# Circuitry.net
KiCad netlist of a schematic drawn in Altium Designer
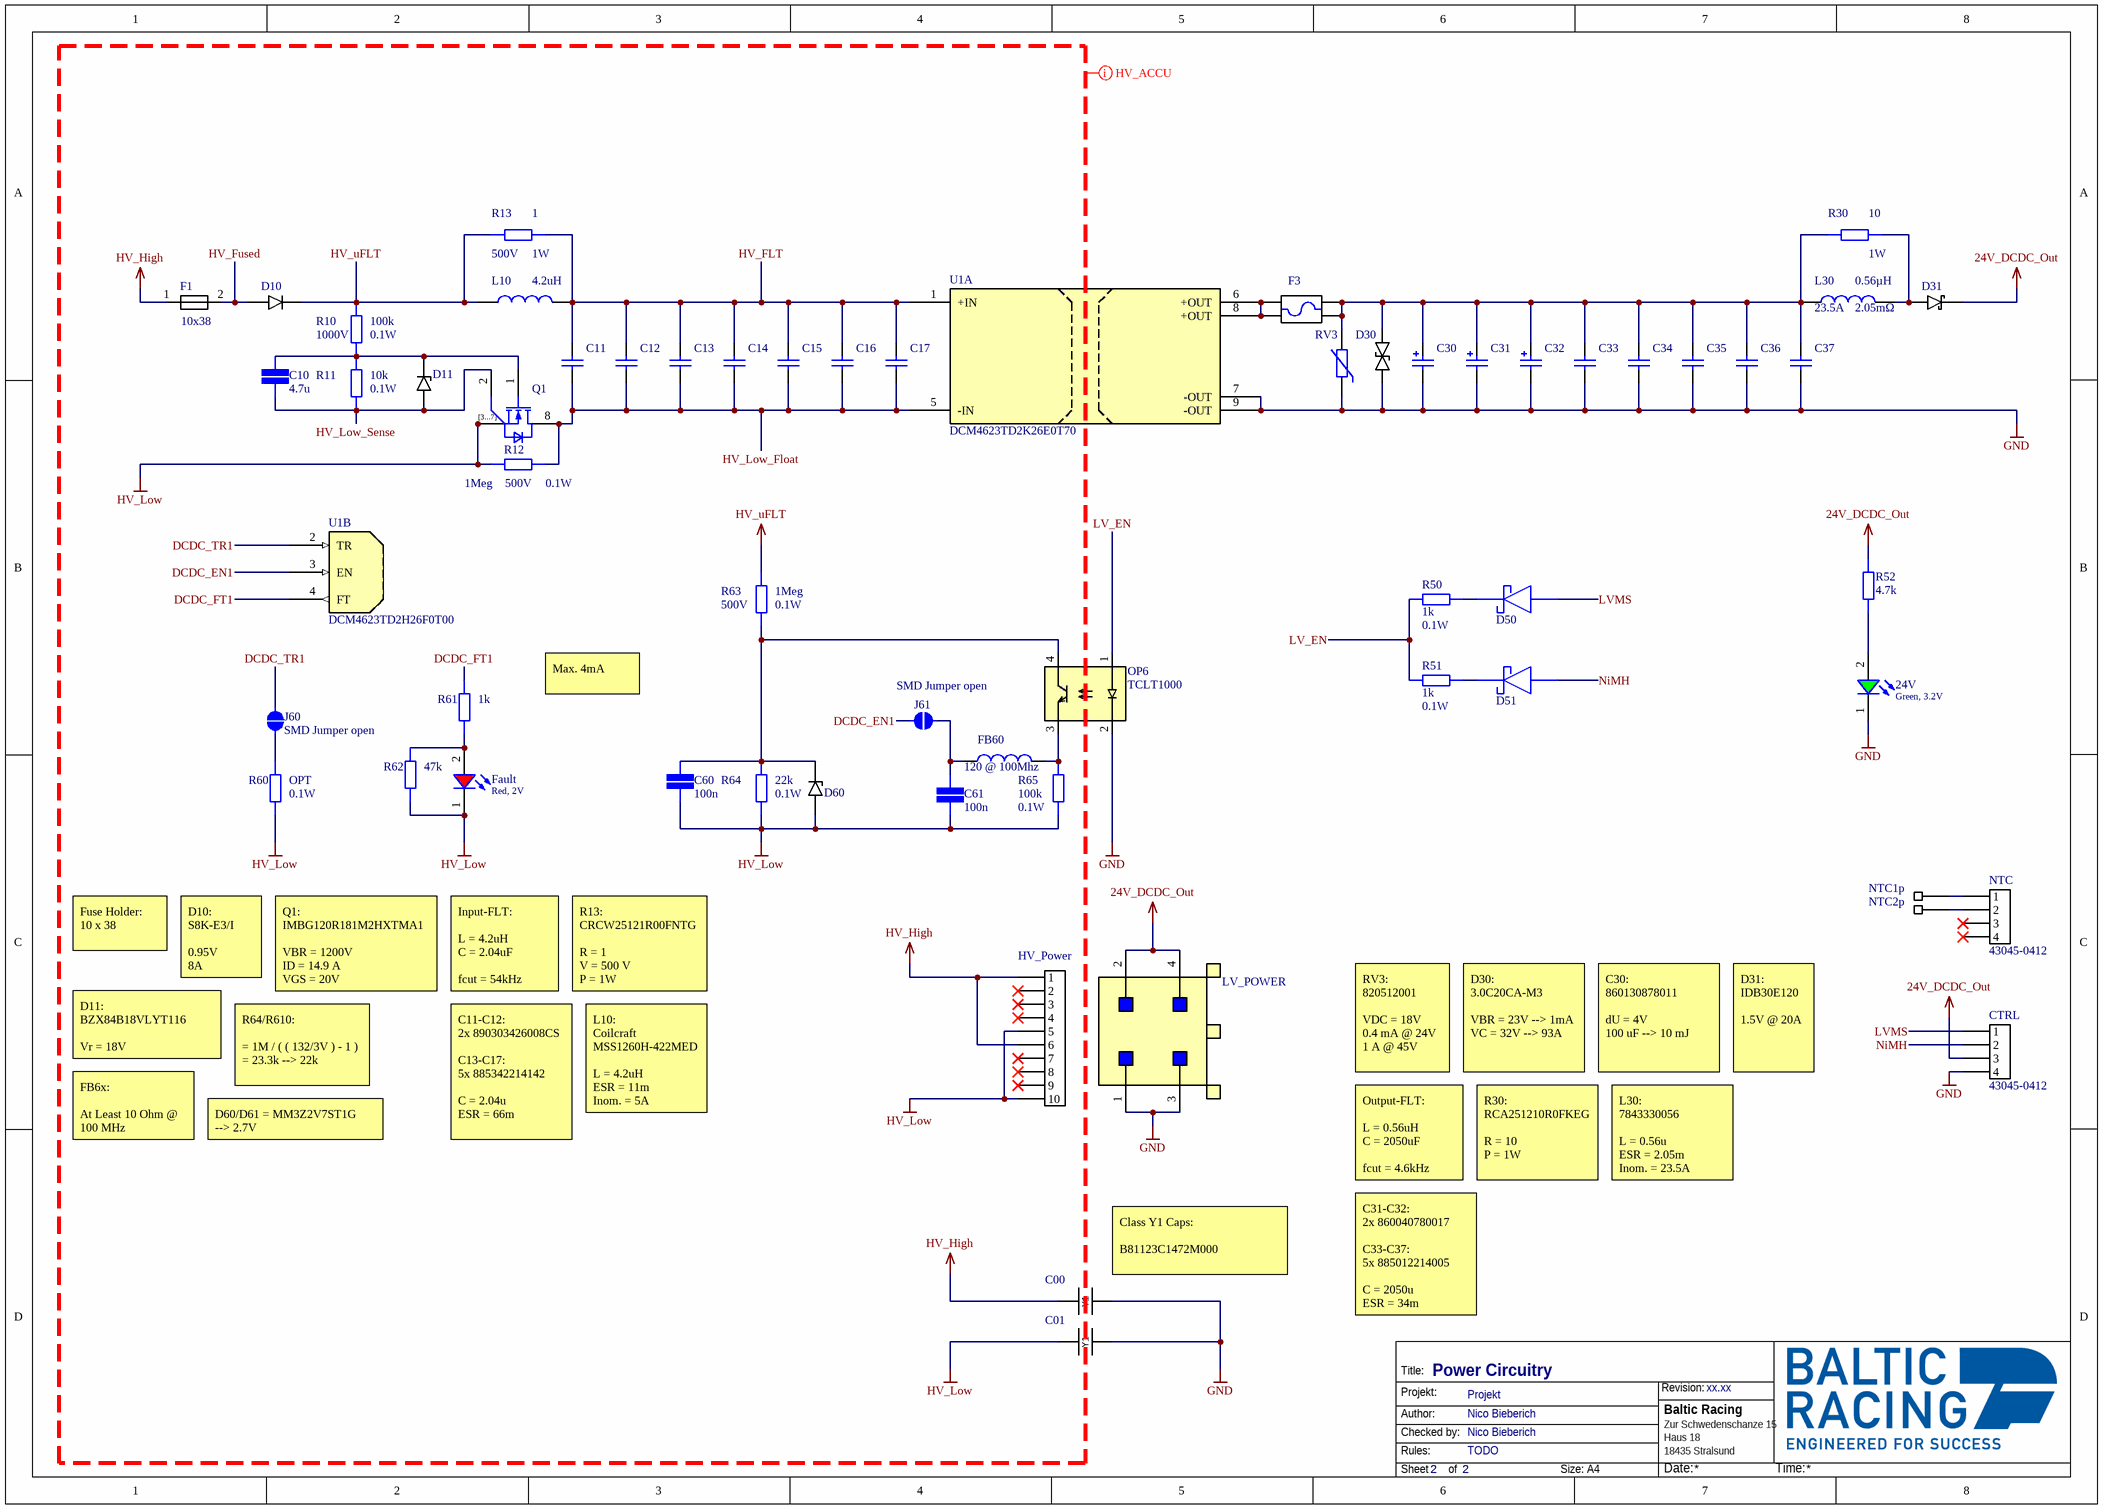
[diagram p0: Circuitry.SchDoc]

(export (version "E")
  (design (tool "Eeschema 10.0.6"))
  (components
    (comp (ref "24V")
      (value "Green, 3.2V")
      (footprint "WL-SMCW_0603_H=0.7mm")
      (description "WL-SMCW SMT Mono-color Chip LED Waterclear, size 0603, Green, 3.2V, 140deg")
      (fields (field (name "PART NUMBER") "150060GS75000") (field (name "PUBLISHER") "Wurth Elektronik"))
      (libsource (lib "Altium_WL-SMCW (rev20a)") (part "150060GS75000"))
    )
    (comp (ref "C00")
      (value "B81123C1472M000")
      (footprint "B81123C1472M000")
      (description "EPCOS/TDK B81123C1472M000\r\nClass Y1 Capacitor")
      (libsource (lib "libNico") (part "B81123C1472M000"))
    )
    (comp (ref "C01")
      (value "B81123C1472M000")
      (footprint "B81123C1472M000")
      (description "EPCOS/TDK B81123C1472M000\r\nClass Y1 Capacitor")
      (libsource (lib "libNico") (part "B81123C1472M000"))
    )
    (comp (ref "C10")
      (value "4.7u")
      (footprint "CAP 1206/3216")
      (description "Capacitor with multiple Footprints")
      (fields (field (name "VOLTAGE") "32V") (field (name "Comment") "SMD Capacitor"))
      (libsource (lib "Standardbauteile") (part "SMD Capacitor"))
    )
    (comp (ref "C11")
      (value "630V DC, 0.47 uF")
      (footprint "WCAP-FTBE_26x9x18")
      (description "WCAP-FTBE Film Capacitors, 26x9x18mm, 630V DC, 0.47 uF")
      (fields (field (name "PART NUMBER") "890303426008CS") (field (name "PUBLISHER") "Wurth Elektronik"))
      (libsource (lib "ALTIUM-WCAP-FTBE-rev17a") (part "890303426008CS"))
    )
    (comp (ref "C12")
      (value "630V DC, 0.47 uF")
      (footprint "WCAP-FTBE_26x9x18")
      (description "WCAP-FTBE Film Capacitors, 26x9x18mm, 630V DC, 0.47 uF")
      (fields (field (name "PART NUMBER") "890303426008CS") (field (name "PUBLISHER") "Wurth Elektronik"))
      (libsource (lib "ALTIUM-WCAP-FTBE-rev17a") (part "890303426008CS"))
    )
    (comp (ref "C13")
      (value "220nF")
      (footprint "WCAP-CSMH_2220_L5.7W5H2")
      (fields
        (field (name "MANUFACTURER PART NUMBER") "885342214142")
        (field (name "MANUFACTURER") "Wurth Elektronik")
      )
      (libsource (lib "Altium_WCAP-CSMH (rev22d)") (part "885342214142"))
    )
    (comp (ref "C14")
      (value "220nF")
      (footprint "WCAP-CSMH_2220_L5.7W5H2")
      (fields
        (field (name "MANUFACTURER PART NUMBER") "885342214142")
        (field (name "MANUFACTURER") "Wurth Elektronik")
      )
      (libsource (lib "Altium_WCAP-CSMH (rev22d)") (part "885342214142"))
    )
    (comp (ref "C15")
      (value "220nF")
      (footprint "WCAP-CSMH_2220_L5.7W5H2")
      (fields
        (field (name "MANUFACTURER PART NUMBER") "885342214142")
        (field (name "MANUFACTURER") "Wurth Elektronik")
      )
      (libsource (lib "Altium_WCAP-CSMH (rev22d)") (part "885342214142"))
    )
    (comp (ref "C16")
      (value "220nF")
      (footprint "WCAP-CSMH_2220_L5.7W5H2")
      (fields
        (field (name "MANUFACTURER PART NUMBER") "885342214142")
        (field (name "MANUFACTURER") "Wurth Elektronik")
      )
      (libsource (lib "Altium_WCAP-CSMH (rev22d)") (part "885342214142"))
    )
    (comp (ref "C17")
      (value "220nF")
      (footprint "WCAP-CSMH_2220_L5.7W5H2")
      (fields
        (field (name "MANUFACTURER PART NUMBER") "885342214142")
        (field (name "MANUFACTURER") "Wurth Elektronik")
      )
      (libsource (lib "Altium_WCAP-CSMH (rev22d)") (part "885342214142"))
    )
    (comp (ref "C30")
      (value "100uF, 100V")
      (footprint "WCAP-ATET_13x25")
      (description "WCAP-ATET THT Aluminum Electrolytic Capacitors, D13mm x L25mm, 100uF, +/-20%, 100VDC")
      (fields (field (name "PART NUMBER") "860130878011") (field (name "PUBLISHER") "Wurth Elektronik"))
      (libsource (lib "Altium_WCAP-ATET (rev19a)") (part "860130878011"))
    )
    (comp (ref "C31")
      (value "1000uF, 63V")
      (footprint "WCAP-ATUL_16x35.5")
      (description "WCAP-ATUL THT Aluminum Electrolytic Capacitors, D16mm x L35.5mm, 1000uF, +/-20%, 63VDC")
      (fields (field (name "PART NUMBER") "860040780017") (field (name "PUBLISHER") "Wurth Elektronik"))
      (libsource (lib "Altium_WCAP-ATUL_rev19a") (part "860040780017"))
    )
    (comp (ref "C32")
      (value "1000uF, 63V")
      (footprint "WCAP-ATUL_16x35.5")
      (description "WCAP-ATUL THT Aluminum Electrolytic Capacitors, D16mm x L35.5mm, 1000uF, +/-20%, 63VDC")
      (fields (field (name "PART NUMBER") "860040780017") (field (name "PUBLISHER") "Wurth Elektronik"))
      (libsource (lib "Altium_WCAP-ATUL_rev19a") (part "860040780017"))
    )
    (comp (ref "C33")
      (value "10uF")
      (footprint "WCAP-CSGP_2220_L5.7W5H2.8")
      (description "WCAP-CSGP Multilayer Ceramic Chip Capacitor, General Purpose, size 2220, X7R Class II, 10uF, 50VDC")
      (fields
        (field (name "MANUFACTURER PART NUMBER") "885012214005")
        (field (name "MANUFACTURER") "Wurth Elektronik")
      )
      (libsource (lib "Altium_WCAP-CSGP (rev24b)") (part "885012214005"))
    )
    (comp (ref "C34")
      (value "10uF")
      (footprint "WCAP-CSGP_2220_L5.7W5H2.8")
      (description "WCAP-CSGP Multilayer Ceramic Chip Capacitor, General Purpose, size 2220, X7R Class II, 10uF, 50VDC")
      (fields
        (field (name "MANUFACTURER PART NUMBER") "885012214005")
        (field (name "MANUFACTURER") "Wurth Elektronik")
      )
      (libsource (lib "Altium_WCAP-CSGP (rev24b)") (part "885012214005"))
    )
    (comp (ref "C35")
      (value "10uF")
      (footprint "WCAP-CSGP_2220_L5.7W5H2.8")
      (description "WCAP-CSGP Multilayer Ceramic Chip Capacitor, General Purpose, size 2220, X7R Class II, 10uF, 50VDC")
      (fields
        (field (name "MANUFACTURER PART NUMBER") "885012214005")
        (field (name "MANUFACTURER") "Wurth Elektronik")
      )
      (libsource (lib "Altium_WCAP-CSGP (rev24b)") (part "885012214005"))
    )
    (comp (ref "C36")
      (value "10uF")
      (footprint "WCAP-CSGP_2220_L5.7W5H2.8")
      (description "WCAP-CSGP Multilayer Ceramic Chip Capacitor, General Purpose, size 2220, X7R Class II, 10uF, 50VDC")
      (fields
        (field (name "MANUFACTURER PART NUMBER") "885012214005")
        (field (name "MANUFACTURER") "Wurth Elektronik")
      )
      (libsource (lib "Altium_WCAP-CSGP (rev24b)") (part "885012214005"))
    )
    (comp (ref "C37")
      (value "10uF")
      (footprint "WCAP-CSGP_2220_L5.7W5H2.8")
      (description "WCAP-CSGP Multilayer Ceramic Chip Capacitor, General Purpose, size 2220, X7R Class II, 10uF, 50VDC")
      (fields
        (field (name "MANUFACTURER PART NUMBER") "885012214005")
        (field (name "MANUFACTURER") "Wurth Elektronik")
      )
      (libsource (lib "Altium_WCAP-CSGP (rev24b)") (part "885012214005"))
    )
    (comp (ref "C60")
      (value "100n")
      (footprint "CAP 0603/1608")
      (description "Capacitor with multiple Footprints")
      (fields (field (name "Comment") "SMD Capacitor"))
      (libsource (lib "Standardbauteile") (part "SMD Capacitor"))
    )
    (comp (ref "C61")
      (value "100n")
      (footprint "CAP 0603/1608")
      (description "Capacitor with multiple Footprints")
      (fields (field (name "Comment") "SMD Capacitor"))
      (libsource (lib "Standardbauteile") (part "SMD Capacitor"))
    )
    (comp (ref "CTRL")
      (value "43045-0412")
      (footprint "43045-0412")
      (libsource (lib "molex_43045") (part "43045-0412"))
    )
    (comp (ref "D10")
      (value "S8K-E3/I")
      (footprint "S8K-E3/I")
      (description "Vishay S8K-E3/I\r\nDiode, 950mV, 8A, 800V")
      (libsource (lib "libNico") (part "S8K-E3/I"))
    )
    (comp (ref "D11")
      (value "BZX84B18VLYT116")
      (footprint "SOT-23-3")
      (description "ROHM BZX84B18VLYT116\r\nZ-Diode, 18V")
      (libsource (lib "libNico") (part "BZX84B18VLYT116"))
    )
    (comp (ref "D30")
      (value "3.0C20CA-M3")
      (footprint "3.0C20CA-M3")
      (description "Vishay 3.0C20CA-M3\r\nBidirect. TVS, 20V, 3kW")
      (libsource (lib "libNico") (part "3.0C20CA-M3"))
    )
    (comp (ref "D31")
      (value "IDB30E120")
      (footprint "Infineon IDB30E120")
      (description "Infineon IDB30E120\r\n1200V, 30A @ 1.7V")
      (libsource (lib "libNico") (part "IDB30E120"))
    )
    (comp (ref "D50")
      (value "CUS521,H3F")
      (footprint "SOD-323-2")
      (description "Toshiba CUS521,H3F\r\nShottky-Diode\r\nForward: 390mV, Reverse: 30V")
      (libsource (lib "libNico") (part "CUS521,H3F"))
    )
    (comp (ref "D51")
      (value "CUS521,H3F")
      (footprint "SOD-323-2")
      (description "Toshiba CUS521,H3F\r\nShottky-Diode\r\nForward: 390mV, Reverse: 30V")
      (libsource (lib "libNico") (part "CUS521,H3F"))
    )
    (comp (ref "D60")
      (value "MM3Z2V7ST1G")
      (footprint "SOD-323-2")
      (description "onsemi MM3Z2V7ST1G\r\nZ-Diode, 2,7V")
      (libsource (lib "libNico") (part "MM3Z2V7ST1G"))
    )
    (comp (ref "F1")
      (value "Fuse 10x38")
      (footprint "Fuse Holder 10x38")
      (fields (field (name "FORMAT") "10x38"))
      (libsource (lib "libNico") (part "Fuse 10x38"))
    )
    (comp (ref "F3")
      (value "Keystone 3557-2")
      (footprint "Keystone 3557-2")
      (description "Keystone 3557-2\r\nFuse Holder")
      (libsource (lib "libNico") (part "Keystone 3557-2"))
    )
    (comp (ref "Fault")
      (value "Red, 2V")
      (footprint "WL-SMCW_0603_H=0.7mm")
      (description "WL-SMCW SMT Mono-color Chip LED Waterclear, size 0603, Red, 2V, 140deg")
      (fields (field (name "PART NUMBER") "150060RS75000") (field (name "PUBLISHER") "Wurth Elektronik"))
      (libsource (lib "Altium_WL-SMCW (rev20a)") (part "150060RS75000"))
    )
    (comp (ref "FB60")
      (value "120 @ 100Mhz")
      (footprint "WE-CBA_0603_L1.6W0.8H0.8_HF/HS/WB")
      (description "WE-CBA SMT EMI Suppression Ferrite Bead, size 0603, 120Ohm, 0.5A")
      (fields
        (field (name "MANUFACTURER PART NUMBER") "782631131")
        (field (name "MANUFACTURER") "Wurth Elektronik")
      )
      (libsource (lib "Altium_WE-CBA (rev22d)") (part "782631131"))
    )
    (comp (ref "HV_Power")
      (value "43045-1012")
      (footprint "43045-1012")
      (libsource (lib "molex_43045") (part "43045-1012"))
    )
    (comp (ref "J60")
      (value "SMD Jumper open")
      (footprint "SMD-JUMPER-OPEN")
      (libsource (lib "Standardbauteile") (part "SMD Jumper open"))
    )
    (comp (ref "J61")
      (value "SMD Jumper open")
      (footprint "SMD-JUMPER-OPEN")
      (libsource (lib "Standardbauteile") (part "SMD Jumper open"))
    )
    (comp (ref "L10")
      (value "4.2uH")
      (footprint "Coilcraft MSS1260H-422MED")
      (description "Coilcraft MSS1260H-422MED\r\nShielded Inductor, 4.2uH, 11mOhm, 5A")
      (fields (field (name "Comment") "MSS1260H-422MED"))
      (libsource (lib "libNico") (part "MSS1260H-422MED"))
    )
    (comp (ref "L30")
      (value "0.56µH, 23.5A")
      (footprint "WE-CHSA_1011")
      (description "WE-CHSA SMT High Current Inductor, size 1011, 0.56µH, 23.5A, 2.05mΩ")
      (fields
        (field (name "MANUFACTURER PART NUMBER") "7843330056")
        (field (name "MANUFACTURER") "Wurth Elektronik")
        (field (name "DC RESISTANCE MAX") "2.05mΩ")
        (field (name "INDUCTANCE") "0.56µH")
        (field (name "RATED CURRENT") "23.5A")
      )
      (libsource (lib "Altium_WE-CHSA (rev22d)") (part "7843330056"))
    )
    (comp (ref "LV_POWER")
      (value "LV_POWER")
      (footprint "1720650004")
      (libsource (lib "libNico") (part "1720650004"))
    )
    (comp (ref "NTC")
      (value "43045-0412")
      (footprint "43045-0412")
      (libsource (lib "molex_43045") (part "43045-0412"))
    )
    (comp (ref "NTC1p")
      (value "Pad")
      (footprint "Generic_Pad_1.5x1.5")
      (description "Pad 1.5mm x 1.5mm")
      (libsource (lib "libNico") (part "Generic_Pad_1.5x1.5"))
    )
    (comp (ref "NTC2p")
      (value "Pad")
      (footprint "Generic_Pad_1.5x1.5")
      (description "Pad 1.5mm x 1.5mm")
      (libsource (lib "libNico") (part "Generic_Pad_1.5x1.5"))
    )
    (comp (ref "OP6")
      (value "TCLT1000")
      (footprint "SOP-4L")
      (description "Opto-Isolator\r\nVishay TLCT100 series\r\n600V, 5mA, V_ISO= 5 kV (RMS)")
      (libsource (lib "libNico") (part "TCLT1000"))
    )
    (comp (ref "Q1")
      (value "IMBG120R181M2H")
      (footprint "TO127P1500X470-8N-2-V1")
      (description "Infineon IMBG120R181M2HXTMA1\r\nCoolSiC, 1200V, 15A, 181.4mOhm")
      (libsource (lib "libNico") (part "IMBG120R181M2H"))
    )
    (comp (ref "R10")
      (value "100k")
      (footprint "STACKPOLE CSR1206")
      (description "Resistor with multiple footprints")
      (fields
        (field (name "VOLTAGE") "1000V")
        (field (name "POWER") "0.1W")
        (field (name "Comment") "SMD Resistor")
      )
      (libsource (lib "Standardbauteile") (part "SMD Resistor"))
    )
    (comp (ref "R11")
      (value "10k")
      (footprint "STACKPOLE CSR1206")
      (description "Resistor with multiple footprints")
      (fields
        (field (name "VOLTAGE") "1000V")
        (field (name "POWER") "0.1W")
        (field (name "Comment") "SMD Resistor")
      )
      (libsource (lib "Standardbauteile") (part "SMD Resistor"))
    )
    (comp (ref "R12")
      (value "1Meg")
      (footprint "STACKPOLE CSRN2512")
      (description "Resistor with multiple footprints")
      (fields
        (field (name "VOLTAGE") "500V")
        (field (name "POWER") "0.1W")
        (field (name "Comment") "SMD Resistor")
      )
      (libsource (lib "Standardbauteile") (part "SMD Resistor"))
    )
    (comp (ref "R13")
      (value "1")
      (footprint "STACKPOLE CSRN2512")
      (description "Resistor with multiple footprints")
      (fields
        (field (name "VOLTAGE") "500V")
        (field (name "POWER") "1W")
        (field (name "Comment") "SMD Resistor")
      )
      (libsource (lib "Standardbauteile") (part "SMD Resistor"))
    )
    (comp (ref "R30")
      (value "10")
      (footprint "STACKPOLE CSRN2512")
      (description "Resistor with multiple footprints")
      (fields (field (name "POWER") "1W") (field (name "Comment") "SMD Resistor"))
      (libsource (lib "Standardbauteile") (part "SMD Resistor"))
    )
    (comp (ref "R50")
      (value "1k")
      (footprint "STACKPOLE CSR0603")
      (description "Resistor with multiple footprints")
      (fields (field (name "POWER") "0.1W") (field (name "Comment") "SMD Resistor"))
      (libsource (lib "Standardbauteile") (part "SMD Resistor"))
    )
    (comp (ref "R51")
      (value "1k")
      (footprint "STACKPOLE CSR0603")
      (description "Resistor with multiple footprints")
      (fields (field (name "POWER") "0.1W") (field (name "Comment") "SMD Resistor"))
      (libsource (lib "Standardbauteile") (part "SMD Resistor"))
    )
    (comp (ref "R52")
      (value "4.7k")
      (footprint "STACKPOLE CSR0603")
      (description "Resistor with multiple footprints")
      (fields (field (name "POWER") "0.1 W") (field (name "Comment") "SMD Resistor"))
      (libsource (lib "Standardbauteile") (part "SMD Resistor"))
    )
    (comp (ref "R60")
      (value "OPT")
      (footprint "STACKPOLE CSR0603")
      (description "Resistor with multiple footprints")
      (fields (field (name "POWER") "0.1W") (field (name "Comment") "SMD Resistor"))
      (libsource (lib "Standardbauteile") (part "SMD Resistor"))
    )
    (comp (ref "R61")
      (value "1k")
      (footprint "STACKPOLE CSR0603")
      (description "Resistor with multiple footprints")
      (fields (field (name "POWER") "0.1W") (field (name "Comment") "SMD Resistor"))
      (libsource (lib "Standardbauteile") (part "SMD Resistor"))
    )
    (comp (ref "R62")
      (value "47k")
      (footprint "STACKPOLE CSR0603")
      (description "Resistor with multiple footprints")
      (fields (field (name "POWER") "0.1W") (field (name "Comment") "SMD Resistor"))
      (libsource (lib "Standardbauteile") (part "SMD Resistor"))
    )
    (comp (ref "R63")
      (value "1Meg")
      (footprint "STACKPOLE CSRN2512")
      (description "Resistor with multiple footprints")
      (fields
        (field (name "VOLTAGE") "500V")
        (field (name "POWER") "0.1W")
        (field (name "Comment") "SMD Resistor")
      )
      (libsource (lib "Standardbauteile") (part "SMD Resistor"))
    )
    (comp (ref "R64")
      (value "22k")
      (footprint "STACKPOLE CSR0603")
      (description "Resistor with multiple footprints")
      (fields (field (name "POWER") "0.1W") (field (name "Comment") "SMD Resistor"))
      (libsource (lib "Standardbauteile") (part "SMD Resistor"))
    )
    (comp (ref "R65")
      (value "100k")
      (footprint "STACKPOLE CSR0603")
      (description "Resistor with multiple footprints")
      (fields (field (name "POWER") "0.1W") (field (name "Comment") "SMD Resistor"))
      (libsource (lib "Standardbauteile") (part "SMD Resistor"))
    )
    (comp (ref "RV3")
      (value "20VAC, 26VDC")
      (footprint "D12.5W5.1H15.5P0.8")
      (description "WE-VD Disk Varistor, THT, 20VAC, 26VDC, 4250pF")
      (fields
        (field (name "MANUFACTURER PART NUMBER") "820512001")
        (field (name "MANUFACTURER") "Wurth Elektronik")
      )
      (libsource (lib "Altium_WE-VD (rev23a)") (part "820512001"))
    )
    (comp (ref "U1")
      (value "DCM4623")
      (footprint "DCM4623")
      (description "VICOR DCM® DC-DC Converter Module")
      (fields (field (name "MODEL") "DCM4623TD2K26E0T70"))
      (libsource (lib "libNico") (part "DCM4623"))
    )
  )
  (nets
    (net (code "1") (name "/DCDC_EN1") (class "Default")
      (node (ref "J61") (pin "2") (pinfunction "2_2") (pintype "passive"))
      (node (ref "U1") (pin "3") (pinfunction "EN_3") (pintype "input"))
    )
    (net (code "2") (name "/DCDC_FT1") (class "Default")
      (node (ref "R61") (pin "2") (pinfunction "2_2") (pintype "passive"))
      (node (ref "U1") (pin "4") (pinfunction "FT_4") (pintype "output"))
    )
    (net (code "3") (name "/DCDC_TR1") (class "Default")
      (node (ref "J60") (pin "2") (pinfunction "2_2") (pintype "passive"))
      (node (ref "U1") (pin "2") (pinfunction "TR_2") (pintype "input"))
    )
    (net (code "4") (name "/HV_FLT") (class "Default")
      (node (ref "C11") (pin "2") (pinfunction "2_2") (pintype "passive"))
      (node (ref "C12") (pin "2") (pinfunction "2_2") (pintype "passive"))
      (node (ref "C13") (pin "2") (pinfunction "2_2") (pintype "passive"))
      (node (ref "C14") (pin "2") (pinfunction "2_2") (pintype "passive"))
      (node (ref "C15") (pin "2") (pinfunction "2_2") (pintype "passive"))
      (node (ref "C16") (pin "2") (pinfunction "2_2") (pintype "passive"))
      (node (ref "C17") (pin "2") (pinfunction "2_2") (pintype "passive"))
      (node (ref "L10") (pin "2") (pinfunction "2_2") (pintype "passive"))
      (node (ref "R13") (pin "1") (pinfunction "1_1") (pintype "passive"))
      (node (ref "U1") (pin "1") (pinfunction "+IN_1") (pintype "power_in"))
    )
    (net (code "5") (name "/HV_Fused") (class "Default")
      (node (ref "D10") (pin "2") (pinfunction "A_2") (pintype "passive"))
      (node (ref "F1") (pin "2") (pinfunction "2_2") (pintype "passive"))
    )
    (net (code "6") (name "/HV_Low_Float") (class "Default")
      (node (ref "C11") (pin "1") (pinfunction "1_1") (pintype "passive"))
      (node (ref "C12") (pin "1") (pinfunction "1_1") (pintype "passive"))
      (node (ref "C13") (pin "1") (pinfunction "1_1") (pintype "passive"))
      (node (ref "C14") (pin "1") (pinfunction "1_1") (pintype "passive"))
      (node (ref "C15") (pin "1") (pinfunction "1_1") (pintype "passive"))
      (node (ref "C16") (pin "1") (pinfunction "1_1") (pintype "passive"))
      (node (ref "C17") (pin "1") (pinfunction "1_1") (pintype "passive"))
      (node (ref "Q1") (pin "8") (pinfunction "DRAIN_8") (pintype "passive"))
      (node (ref "R12") (pin "1") (pinfunction "1_1") (pintype "passive"))
      (node (ref "U1") (pin "5") (pinfunction "-IN_5") (pintype "passive"))
    )
    (net (code "7") (name "/HV_Low_Sense") (class "Default")
      (node (ref "C10") (pin "1") (pinfunction "1_1") (pintype "passive"))
      (node (ref "D11") (pin "1") (pinfunction "A_1") (pintype "passive"))
      (node (ref "Q1") (pin "2") (pinfunction "SENSE_2") (pintype "passive"))
      (node (ref "R11") (pin "1") (pinfunction "1_1") (pintype "passive"))
    )
    (net (code "8") (name "/LVMS") (class "Default")
      (node (ref "CTRL") (pin "1") (pinfunction "1_1") (pintype "passive"))
      (node (ref "D50") (pin "2A") (pinfunction "A_2A") (pintype "passive"))
    )
    (net (code "9") (name "/LV_EN") (class "Default")
      (node (ref "OP6") (pin "1") (pinfunction "DA_1") (pintype "passive"))
      (node (ref "R50") (pin "2") (pinfunction "2_2") (pintype "passive"))
      (node (ref "R51") (pin "2") (pinfunction "2_2") (pintype "passive"))
    )
    (net (code "10") (name "/NiMH") (class "Default")
      (node (ref "CTRL") (pin "2") (pinfunction "2_2") (pintype "passive"))
      (node (ref "D51") (pin "2A") (pinfunction "A_2A") (pintype "passive"))
    )
    (net (code "11") (name "24V_DCDC_Out") (class "Default")
      (node (ref "CTRL") (pin "3") (pinfunction "3_3") (pintype "passive"))
      (node (ref "D31") (pin "2") (pinfunction "C_2") (pintype "passive"))
      (node (ref "LV_POWER") (pin "2") (pinfunction "2_2") (pintype "passive"))
      (node (ref "LV_POWER") (pin "4") (pinfunction "4_4") (pintype "passive"))
      (node (ref "R52") (pin "2") (pinfunction "2_2") (pintype "passive"))
    )
    (net (code "12") (name "GND") (class "Default")
      (node (ref "24V") (pin "1") (pinfunction "K_1") (pintype "passive"))
      (node (ref "C00") (pin "2") (pinfunction "2_2") (pintype "passive"))
      (node (ref "C01") (pin "2") (pinfunction "2_2") (pintype "passive"))
      (node (ref "C30") (pin "1") (pinfunction "N_1") (pintype "passive"))
      (node (ref "C31") (pin "1") (pinfunction "N_1") (pintype "passive"))
      (node (ref "C32") (pin "1") (pinfunction "N_1") (pintype "passive"))
      (node (ref "C33") (pin "1") (pinfunction "1_1") (pintype "passive"))
      (node (ref "C34") (pin "1") (pinfunction "1_1") (pintype "passive"))
      (node (ref "C35") (pin "1") (pinfunction "1_1") (pintype "passive"))
      (node (ref "C36") (pin "1") (pinfunction "1_1") (pintype "passive"))
      (node (ref "C37") (pin "1") (pinfunction "1_1") (pintype "passive"))
      (node (ref "CTRL") (pin "4") (pinfunction "4_4") (pintype "passive"))
      (node (ref "D30") (pin "1") (pinfunction "1_1") (pintype "passive"))
      (node (ref "LV_POWER") (pin "1") (pinfunction "1_1") (pintype "passive"))
      (node (ref "LV_POWER") (pin "3") (pinfunction "3_3") (pintype "passive"))
      (node (ref "OP6") (pin "2") (pinfunction "DC_2") (pintype "passive"))
      (node (ref "RV3") (pin "1") (pinfunction "1_1") (pintype "passive"))
      (node (ref "U1") (pin "7") (pinfunction "-OUT_7") (pintype "passive"))
      (node (ref "U1") (pin "9") (pinfunction "-OUT_9") (pintype "passive"))
    )
    (net (code "13") (name "HV_High") (class "Default")
      (node (ref "C00") (pin "1") (pinfunction "1_1") (pintype "passive"))
      (node (ref "F1") (pin "1") (pinfunction "1_1") (pintype "passive"))
      (node (ref "HV_Power") (pin "1") (pinfunction "1_1") (pintype "passive"))
      (node (ref "HV_Power") (pin "6") (pinfunction "6_6") (pintype "passive"))
    )
    (net (code "14") (name "HV_Low") (class "Default")
      (node (ref "C01") (pin "1") (pinfunction "1_1") (pintype "passive"))
      (node (ref "C60") (pin "1") (pinfunction "1_1") (pintype "passive"))
      (node (ref "C61") (pin "1") (pinfunction "1_1") (pintype "passive"))
      (node (ref "D60") (pin "2A") (pinfunction "A_2A") (pintype "passive"))
      (node (ref "Fault") (pin "1") (pinfunction "K_1") (pintype "passive"))
      (node (ref "HV_Power") (pin "10") (pinfunction "10_10") (pintype "passive"))
      (node (ref "HV_Power") (pin "5") (pinfunction "5_5") (pintype "passive"))
      (node (ref "Q1") (pin "3") (pinfunction "SOURCE1_3") (pintype "passive"))
      (node (ref "Q1") (pin "4") (pinfunction "SOURCE2_4") (pintype "passive"))
      (node (ref "Q1") (pin "5") (pinfunction "SOURCE3_5") (pintype "passive"))
      (node (ref "Q1") (pin "6") (pinfunction "SOURCE4_6") (pintype "passive"))
      (node (ref "Q1") (pin "7") (pinfunction "SOURCE5_7") (pintype "passive"))
      (node (ref "R12") (pin "2") (pinfunction "2_2") (pintype "passive"))
      (node (ref "R60") (pin "1") (pinfunction "1_1") (pintype "passive"))
      (node (ref "R62") (pin "1") (pinfunction "1_1") (pintype "passive"))
      (node (ref "R64") (pin "1") (pinfunction "1_1") (pintype "passive"))
      (node (ref "R65") (pin "1") (pinfunction "1_1") (pintype "passive"))
    )
    (net (code "15") (name "HV_uFLT") (class "Default")
      (node (ref "D10") (pin "1") (pinfunction "C_1") (pintype "passive"))
      (node (ref "L10") (pin "1") (pinfunction "1_1") (pintype "passive"))
      (node (ref "R10") (pin "2") (pinfunction "2_2") (pintype "passive"))
      (node (ref "R13") (pin "2") (pinfunction "2_2") (pintype "passive"))
      (node (ref "R63") (pin "2") (pinfunction "2_2") (pintype "passive"))
    )
    (net (code "16") (name "Net-(24V-A)") (class "Default")
      (node (ref "24V") (pin "2") (pinfunction "A_2") (pintype "passive"))
      (node (ref "R52") (pin "1") (pinfunction "1_1") (pintype "passive"))
    )
    (net (code "17") (name "Net-(C30-P)") (class "Default")
      (node (ref "C30") (pin "2") (pinfunction "P_2") (pintype "passive"))
      (node (ref "C31") (pin "2") (pinfunction "P_2") (pintype "passive"))
      (node (ref "C32") (pin "2") (pinfunction "P_2") (pintype "passive"))
      (node (ref "C33") (pin "2") (pinfunction "2_2") (pintype "passive"))
      (node (ref "C34") (pin "2") (pinfunction "2_2") (pintype "passive"))
      (node (ref "C35") (pin "2") (pinfunction "2_2") (pintype "passive"))
      (node (ref "C36") (pin "2") (pinfunction "2_2") (pintype "passive"))
      (node (ref "C37") (pin "2") (pinfunction "2_2") (pintype "passive"))
      (node (ref "D30") (pin "2") (pinfunction "2_2") (pintype "passive"))
      (node (ref "F3") (pin "O1") (pinfunction "O1_O1") (pintype "passive"))
      (node (ref "F3") (pin "O2") (pinfunction "O2_O2") (pintype "passive"))
      (node (ref "L30") (pin "1") (pinfunction "1_1") (pintype "passive"))
      (node (ref "R30") (pin "2") (pinfunction "2_2") (pintype "passive"))
      (node (ref "RV3") (pin "2") (pinfunction "2_2") (pintype "passive"))
    )
    (net (code "18") (name "Net-(C61-Pad2)") (class "Default")
      (node (ref "C61") (pin "2") (pinfunction "2_2") (pintype "passive"))
      (node (ref "FB60") (pin "1") (pinfunction "1_1") (pintype "passive"))
      (node (ref "J61") (pin "1") (pinfunction "1_1") (pintype "passive"))
    )
    (net (code "19") (name "Net-(D11-C)") (class "Default")
      (node (ref "C10") (pin "2") (pinfunction "2_2") (pintype "passive"))
      (node (ref "D11") (pin "3") (pinfunction "C_3") (pintype "passive"))
      (node (ref "Q1") (pin "1") (pinfunction "GATE_1") (pintype "passive"))
      (node (ref "R10") (pin "1") (pinfunction "1_1") (pintype "passive"))
      (node (ref "R11") (pin "2") (pinfunction "2_2") (pintype "passive"))
    )
    (net (code "20") (name "Net-(D31-A)") (class "Default")
      (node (ref "D31") (pin "3") (pinfunction "A_3") (pintype "passive"))
      (node (ref "L30") (pin "2") (pinfunction "2_2") (pintype "passive"))
      (node (ref "R30") (pin "1") (pinfunction "1_1") (pintype "passive"))
    )
    (net (code "21") (name "Net-(D50-C)") (class "Default")
      (node (ref "D50") (pin "1C") (pinfunction "C_1C") (pintype "passive"))
      (node (ref "R50") (pin "1") (pinfunction "1_1") (pintype "passive"))
    )
    (net (code "22") (name "Net-(D51-C)") (class "Default")
      (node (ref "D51") (pin "1C") (pinfunction "C_1C") (pintype "passive"))
      (node (ref "R51") (pin "1") (pinfunction "1_1") (pintype "passive"))
    )
    (net (code "23") (name "Net-(D60-C)") (class "Default")
      (node (ref "C60") (pin "2") (pinfunction "2_2") (pintype "passive"))
      (node (ref "D60") (pin "1C") (pinfunction "C_1C") (pintype "passive"))
      (node (ref "OP6") (pin "4") (pinfunction "TC_4") (pintype "passive"))
      (node (ref "R63") (pin "1") (pinfunction "1_1") (pintype "passive"))
      (node (ref "R64") (pin "2") (pinfunction "2_2") (pintype "passive"))
    )
    (net (code "24") (name "Net-(F3-PadI1)") (class "Default")
      (node (ref "F3") (pin "I1") (pinfunction "I1_I1") (pintype "passive"))
      (node (ref "F3") (pin "I2") (pinfunction "I2_I2") (pintype "passive"))
      (node (ref "U1") (pin "6") (pinfunction "+OUT_6") (pintype "power_in"))
      (node (ref "U1") (pin "8") (pinfunction "+OUT_8") (pintype "power_in"))
    )
    (net (code "25") (name "Net-(Fault-A)") (class "Default")
      (node (ref "Fault") (pin "2") (pinfunction "A_2") (pintype "passive"))
      (node (ref "R61") (pin "1") (pinfunction "1_1") (pintype "passive"))
      (node (ref "R62") (pin "2") (pinfunction "2_2") (pintype "passive"))
    )
    (net (code "26") (name "Net-(J60-Pad1)") (class "Default")
      (node (ref "J60") (pin "1") (pinfunction "1_1") (pintype "passive"))
      (node (ref "R60") (pin "2") (pinfunction "2_2") (pintype "passive"))
    )
    (net (code "27") (name "Net-(NTC-Pad1)") (class "Default")
      (node (ref "NTC") (pin "1") (pinfunction "1_1") (pintype "passive"))
      (node (ref "NTC1p") (pin "P") (pinfunction "Pad_P") (pintype "passive"))
    )
    (net (code "28") (name "Net-(NTC-Pad2)") (class "Default")
      (node (ref "NTC") (pin "2") (pinfunction "2_2") (pintype "passive"))
      (node (ref "NTC2p") (pin "P") (pinfunction "Pad_P") (pintype "passive"))
    )
    (net (code "29") (name "Net-(OP6-TE)") (class "Default")
      (node (ref "FB60") (pin "2") (pinfunction "2_2") (pintype "passive"))
      (node (ref "OP6") (pin "3") (pinfunction "TE_3") (pintype "passive"))
      (node (ref "R65") (pin "2") (pinfunction "2_2") (pintype "passive"))
    )
    (net (code "30") (name "unconnected-(HV_Power-Pad2)") (class "Default")
      (node (ref "HV_Power") (pin "2") (pinfunction "2_2") (pintype "passive+no_connect"))
    )
    (net (code "31") (name "unconnected-(HV_Power-Pad3)") (class "Default")
      (node (ref "HV_Power") (pin "3") (pinfunction "3_3") (pintype "passive+no_connect"))
    )
    (net (code "32") (name "unconnected-(HV_Power-Pad4)") (class "Default")
      (node (ref "HV_Power") (pin "4") (pinfunction "4_4") (pintype "passive+no_connect"))
    )
    (net (code "33") (name "unconnected-(HV_Power-Pad7)") (class "Default")
      (node (ref "HV_Power") (pin "7") (pinfunction "7_7") (pintype "passive+no_connect"))
    )
    (net (code "34") (name "unconnected-(HV_Power-Pad8)") (class "Default")
      (node (ref "HV_Power") (pin "8") (pinfunction "8_8") (pintype "passive+no_connect"))
    )
    (net (code "35") (name "unconnected-(HV_Power-Pad9)") (class "Default")
      (node (ref "HV_Power") (pin "9") (pinfunction "9_9") (pintype "passive+no_connect"))
    )
    (net (code "36") (name "unconnected-(NTC-Pad3)") (class "Default")
      (node (ref "NTC") (pin "3") (pinfunction "3_3") (pintype "passive+no_connect"))
    )
    (net (code "37") (name "unconnected-(NTC-Pad4)") (class "Default")
      (node (ref "NTC") (pin "4") (pinfunction "4_4") (pintype "passive+no_connect"))
    )
  )
)
